# 5v_PS_V02.net
KiCad netlist of a schematic drawn in EAGLE
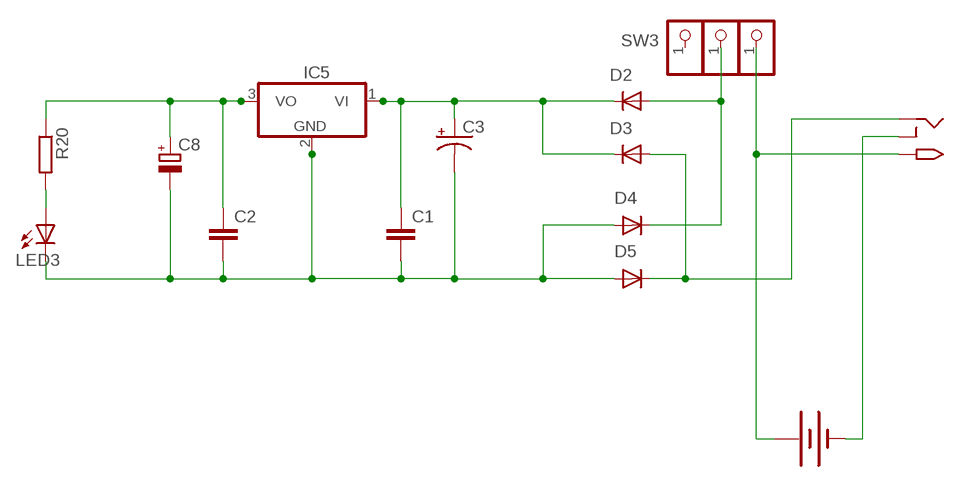
[diagram p0: schematic, sheet 1]

(export (version "E")
  (design (tool "Eeschema 10.0.6"))
  (components
    (comp (ref "BAT1")
      (value "BATTERY")
      (footprint "eagle-import:PP3_BATTERBOX")
      (libsource (lib "eagle-import") (part "BATTERY"))
    )
    (comp (ref "C1")
      (value "330nf")
      (footprint "eagle-import:C025-024X044")
      (libsource (lib "eagle-import") (part "C-EU025-024X044"))
    )
    (comp (ref "C2")
      (value "100nf")
      (footprint "eagle-import:C025-024X044")
      (libsource (lib "eagle-import") (part "C-EU025-024X044"))
    )
    (comp (ref "C3")
      (value "2200uf")
      (footprint "eagle-import:E5-10,5")
      (libsource (lib "eagle-import") (part "CPOL-USE5-10.5"))
    )
    (comp (ref "C8")
      (value "10uf")
      (footprint "eagle-import:E2,5-7")
      (libsource (lib "eagle-import") (part "CPOL-EUE2.5-7"))
    )
    (comp (ref "D2")
      (value "1N4004")
      (footprint "eagle-import:DO-VERT")
      (libsource (lib "eagle-import") (part "1N4004"))
    )
    (comp (ref "D3")
      (value "1N4004")
      (footprint "eagle-import:DO-VERT")
      (libsource (lib "eagle-import") (part "1N4004"))
    )
    (comp (ref "D4")
      (value "1N4004")
      (footprint "eagle-import:DO-VERT")
      (libsource (lib "eagle-import") (part "1N4004"))
    )
    (comp (ref "D5")
      (value "1N4004")
      (footprint "eagle-import:DO-VERT")
      (libsource (lib "eagle-import") (part "1N4004"))
    )
    (comp (ref "IC5")
      (value "7805TV")
      (footprint "eagle-import:TO220V")
      (libsource (lib "eagle-import") (part "78TV05"))
    )
    (comp (ref "J1")
      (value "2.1MMJACKTHM")
      (footprint "eagle-import:PJ-102A")
      (libsource (lib "eagle-import") (part "2.1MMJACKTHM"))
    )
    (comp (ref "LED3")
      (value "LED3MM")
      (footprint "eagle-import:LED3MM")
      (libsource (lib "eagle-import") (part "LED3MM"))
    )
    (comp (ref "ONOFF")
      (value "PINHD-1X1")
      (footprint "eagle-import:1X01")
      (libsource (lib "eagle-import") (part "PINHD-1X1"))
    )
    (comp (ref "R20")
      (value "1k")
      (footprint "eagle-import:0207_7")
      (libsource (lib "eagle-import") (part "R-EU_0207/7"))
    )
    (comp (ref "SW2")
      (value "PINHD-1X1")
      (footprint "eagle-import:1X01")
      (libsource (lib "eagle-import") (part "PINHD-1X1"))
    )
    (comp (ref "SW3")
      (value "PINHD-1X1")
      (footprint "eagle-import:1X01")
      (libsource (lib "eagle-import") (part "PINHD-1X1"))
    )
  )
  (nets
    (net (code "1") (name "Net-(BAT1-+)") (class "Default")
      (node (ref "BAT1") (pin "9V") (pinfunction "+_9V") (pintype "power_in"))
      (node (ref "J1") (pin "TIP") (pinfunction "TIP_TIP") (pintype "bidirectional"))
      (node (ref "SW2") (pin "1") (pinfunction "1_1") (pintype "passive"))
    )
    (net (code "2") (name "Net-(BAT1--)") (class "Default")
      (node (ref "BAT1") (pin "0V") (pinfunction "-_0V") (pintype "power_in"))
      (node (ref "J1") (pin "RING_SW") (pinfunction "RING_SW_RING_SW") (pintype "bidirectional"))
    )
    (net (code "3") (name "Net-(D2-PadA)") (class "Default")
      (node (ref "D2") (pin "A") (pinfunction "A_A") (pintype "passive"))
      (node (ref "D4") (pin "C") (pinfunction "C_C") (pintype "passive"))
      (node (ref "ONOFF") (pin "1") (pinfunction "1_1") (pintype "passive"))
    )
    (net (code "4") (name "Net-(D3-PadA)") (class "Default")
      (node (ref "D3") (pin "A") (pinfunction "A_A") (pintype "passive"))
      (node (ref "D5") (pin "C") (pinfunction "C_C") (pintype "passive"))
      (node (ref "J1") (pin "RING") (pinfunction "RING_RING") (pintype "bidirectional"))
    )
    (net (code "5") (name "Net-(IC5-GND)") (class "Default")
      (node (ref "C1") (pin "2") (pinfunction "2_2") (pintype "passive"))
      (node (ref "C2") (pin "2") (pinfunction "2_2") (pintype "passive"))
      (node (ref "C3") (pin "-") (pinfunction "-_-") (pintype "passive"))
      (node (ref "C8") (pin "-") (pinfunction "-_-") (pintype "passive"))
      (node (ref "D4") (pin "A") (pinfunction "A_A") (pintype "passive"))
      (node (ref "D5") (pin "A") (pinfunction "A_A") (pintype "passive"))
      (node (ref "IC5") (pin "2") (pinfunction "GND_2") (pintype "passive"))
      (node (ref "LED3") (pin "K") (pinfunction "C_K") (pintype "passive"))
    )
    (net (code "6") (name "Net-(IC5-VI)") (class "Default")
      (node (ref "C1") (pin "1") (pinfunction "1_1") (pintype "passive"))
      (node (ref "C3") (pin "+") (pinfunction "+_+") (pintype "passive"))
      (node (ref "D2") (pin "C") (pinfunction "C_C") (pintype "passive"))
      (node (ref "D3") (pin "C") (pinfunction "C_C") (pintype "passive"))
      (node (ref "IC5") (pin "1") (pinfunction "VI_1") (pintype "input"))
    )
    (net (code "7") (name "Net-(IC5-VO)") (class "Default")
      (node (ref "C2") (pin "1") (pinfunction "1_1") (pintype "passive"))
      (node (ref "C8") (pin "+") (pinfunction "+_+") (pintype "passive"))
      (node (ref "IC5") (pin "3") (pinfunction "VO_3") (pintype "passive"))
      (node (ref "R20") (pin "1") (pinfunction "1_1") (pintype "passive"))
    )
    (net (code "8") (name "Net-(LED3-PadA)") (class "Default")
      (node (ref "LED3") (pin "A") (pinfunction "A_A") (pintype "passive"))
      (node (ref "R20") (pin "2") (pinfunction "2_2") (pintype "passive"))
    )
    (net (code "9") (name "unconnected-(SW3-Pad1)") (class "Default")
      (node (ref "SW3") (pin "1") (pinfunction "1_1") (pintype "passive"))
    )
  )
)
